# power.net
KiCad netlist of a schematic drawn in Altium Designer
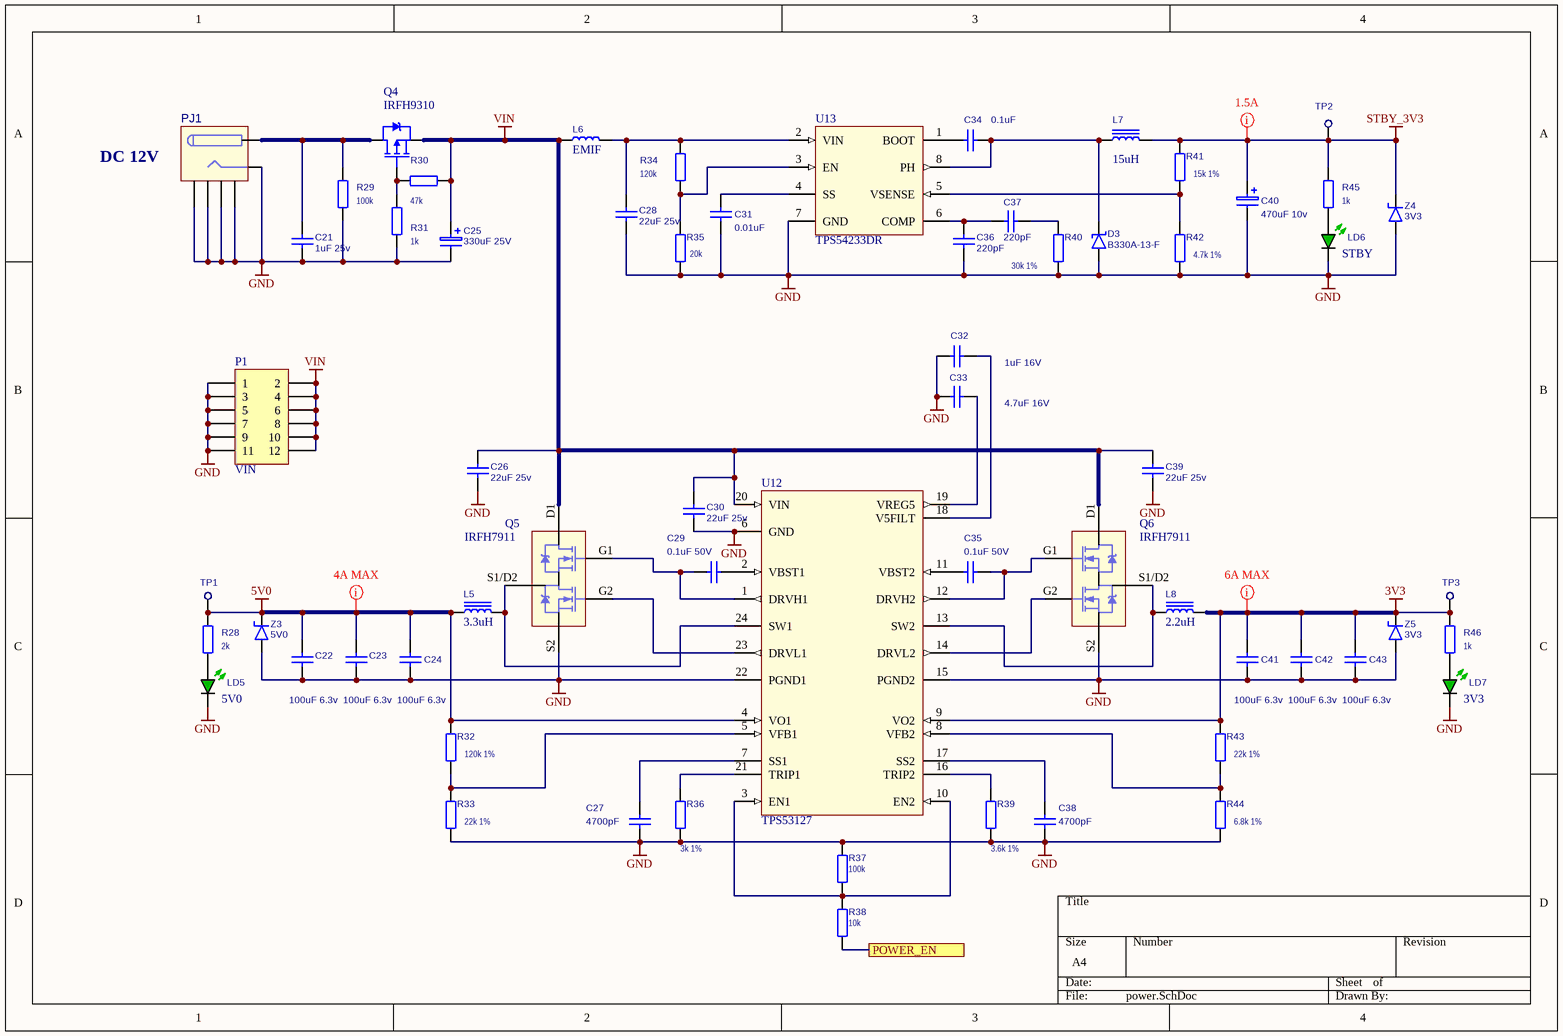
[diagram p0: power.SchDoc]

(export (version "E")
  (design (tool "Eeschema 10.0.6"))
  (components
    (comp (ref "C21")
      (value "1uF 25v")
      (footprint "C0805")
      (description "CAP_NPOL")
      (fields (field (name "Comment") "CL21B105KAFNNNE"))
      (libsource (lib "capacitors") (part "CAP_NPOL"))
    )
    (comp (ref "C22")
      (value "100uF 6.3v")
      (footprint "C1206")
      (description "CAP_NPOL")
      (fields (field (name "Comment") "CL31A107MQHNNNE"))
      (libsource (lib "capacitors") (part "CAP_NPOL"))
    )
    (comp (ref "C23")
      (value "100uF 6.3v")
      (footprint "C1206")
      (description "CAP_NPOL")
      (fields (field (name "Comment") "CL31A107MQHNNNE"))
      (libsource (lib "capacitors") (part "CAP_NPOL"))
    )
    (comp (ref "C24")
      (value "100uF 6.3v")
      (footprint "C1206")
      (description "CAP_NPOL")
      (fields (field (name "Comment") "CL31A107MQHNNNE"))
      (libsource (lib "capacitors") (part "CAP_NPOL"))
    )
    (comp (ref "C25")
      (value "330uF 25V")
      (footprint "Capacitors:R08H04")
      (description "CAP_POL")
      (fields (field (name "Comment") "ECAP 330/25V 0811 105'C"))
      (libsource (lib "capacitors") (part "CAP_POL"))
    )
    (comp (ref "C26")
      (value "22uF 25v")
      (footprint "Capacitors:C0805")
      (description "CAP_NPOL")
      (fields (field (name "Comment") "CL21A226MAQNNNE"))
      (libsource (lib "capacitors") (part "CAP_NPOL"))
    )
    (comp (ref "C27")
      (value "4700pF")
      (footprint "Capacitors:C0603")
      (description "CAP_NPOL")
      (fields (field (name "Comment") "CL10B472KB8NNNC"))
      (libsource (lib "capacitors") (part "CAP_NPOL"))
    )
    (comp (ref "C28")
      (value "22uF 25v")
      (footprint "Capacitors:C0805")
      (description "CAP_NPOL")
      (fields (field (name "Comment") "CL21A226MAQNNNE"))
      (libsource (lib "capacitors") (part "CAP_NPOL"))
    )
    (comp (ref "C29")
      (value "0.1uF 50V")
      (footprint "Capacitors:C0603")
      (description "CAP_NPOL")
      (fields (field (name "Comment") "C1608X7R1H104K080AA"))
      (libsource (lib "capacitors") (part "CAP_NPOL"))
    )
    (comp (ref "C30")
      (value "22uF 25v")
      (footprint "Capacitors:C0805")
      (description "CAP_NPOL")
      (fields (field (name "Comment") "CL21A226MAQNNNE"))
      (libsource (lib "capacitors") (part "CAP_NPOL"))
    )
    (comp (ref "C31")
      (value "0.01uF")
      (footprint "Capacitors:C0603")
      (description "CAP_NPOL")
      (fields (field (name "Comment") "CL10B103KB8NNNC"))
      (libsource (lib "capacitors") (part "CAP_NPOL"))
    )
    (comp (ref "C32")
      (value "1uF 16V")
      (footprint "Capacitors:C0603")
      (description "CAP_NPOL")
      (fields (field (name "Comment") "GRM188R61H105KAALD"))
      (libsource (lib "capacitors") (part "CAP_NPOL"))
    )
    (comp (ref "C33")
      (value "4.7uF 16V")
      (footprint "Capacitors:C0805")
      (description "CAP_NPOL")
      (fields (field (name "Comment") "CL21A475KOFNNNE"))
      (libsource (lib "capacitors") (part "CAP_NPOL"))
    )
    (comp (ref "C34")
      (value "0.1uF")
      (footprint "Capacitors:C0603")
      (description "CAP_NPOL")
      (fields (field (name "Comment") "C1608X7R1H104K080AA"))
      (libsource (lib "capacitors") (part "CAP_NPOL"))
    )
    (comp (ref "C35")
      (value "0.1uF 50V")
      (footprint "Capacitors:C0603")
      (description "CAP_NPOL")
      (fields (field (name "Comment") "C1608X7R1H104K080AA"))
      (libsource (lib "capacitors") (part "CAP_NPOL"))
    )
    (comp (ref "C36")
      (value "220pF")
      (footprint "Capacitors:C0603")
      (description "CAP_NPOL")
      (fields (field (name "Comment") "CL10C221JB8NNNC"))
      (libsource (lib "capacitors") (part "CAP_NPOL"))
    )
    (comp (ref "C37")
      (value "220pF")
      (footprint "Capacitors:C0603")
      (description "CAP_NPOL")
      (fields (field (name "Comment") "CL10C221JB8NNNC"))
      (libsource (lib "capacitors") (part "CAP_NPOL"))
    )
    (comp (ref "C38")
      (value "4700pF")
      (footprint "Capacitors:C0603")
      (description "CAP_NPOL")
      (fields (field (name "Comment") "CL10B472KB8NNNC"))
      (libsource (lib "capacitors") (part "CAP_NPOL"))
    )
    (comp (ref "C39")
      (value "22uF 25v")
      (footprint "Capacitors:C0805")
      (description "CAP_NPOL")
      (fields (field (name "Comment") "CL21A226MAQNNNE"))
      (libsource (lib "capacitors") (part "CAP_NPOL"))
    )
    (comp (ref "C40")
      (value "470uF 10v")
      (footprint "Capacitors:R06H11")
      (description "CAP_POL")
      (fields (field (name "Comment") "ECAP 470/10V 0611 105'C"))
      (libsource (lib "capacitors") (part "CAP_POL"))
    )
    (comp (ref "C41")
      (value "100uF 6.3v")
      (footprint "C1206")
      (description "CAP_NPOL")
      (fields (field (name "Comment") "CL31A107MQHNNNE"))
      (libsource (lib "capacitors") (part "CAP_NPOL"))
    )
    (comp (ref "C42")
      (value "100uF 6.3v")
      (footprint "C1206")
      (description "CAP_NPOL")
      (fields (field (name "Comment") "CL31A107MQHNNNE"))
      (libsource (lib "capacitors") (part "CAP_NPOL"))
    )
    (comp (ref "C43")
      (value "100uF 6.3v")
      (footprint "C1206")
      (description "CAP_NPOL")
      (fields (field (name "Comment") "CL31A107MQHNNNE"))
      (libsource (lib "capacitors") (part "CAP_NPOL"))
    )
    (comp (ref "D3")
      (value "B330A-13-F")
      (footprint "Diodes:SMA")
      (description "SHOTTKY")
      (libsource (lib "diodes") (part "SHOTTKY"))
    )
    (comp (ref "L5")
      (value "3.3uH")
      (footprint "IHLP-2525CZ")
      (description "IND_W_IRON")
      (fields (field (name "Comment") "IHLP2525CZER3R3M01"))
      (libsource (lib "inductors") (part "IND_W_IRON"))
    )
    (comp (ref "L6")
      (value "EMIF")
      (footprint "IND0805")
      (description "IND_WO_IRON")
      (fields (field (name "Comment") "BLM21PG221SN1D"))
      (libsource (lib "inductors") (part "IND_WO_IRON"))
    )
    (comp (ref "L7")
      (value "15uH")
      (footprint "CDRH104R")
      (fields (field (name "Comment") "CDRH104RNP-150NC"))
      (libsource (lib "inductors") (part "IND_W_IRON"))
    )
    (comp (ref "L8")
      (value "2.2uH")
      (footprint "IHLP-2525CZ")
      (description "IND_W_IRON")
      (fields (field (name "Comment") "IHLP2525CZER2R2M01"))
      (libsource (lib "inductors") (part "IND_W_IRON"))
    )
    (comp (ref "LD5")
      (value "5V0")
      (footprint "LED0805")
      (description "LED Green")
      (fields (field (name "Comment") "LED_G"))
      (libsource (lib "leds") (part "LED_GREEN"))
    )
    (comp (ref "LD6")
      (value "STBY")
      (footprint "Leds:LED0805")
      (description "LED Green")
      (fields (field (name "Comment") "LED_G"))
      (libsource (lib "leds") (part "LED_GREEN"))
    )
    (comp (ref "LD7")
      (value "3V3")
      (footprint "LED0805")
      (description "LED Green")
      (fields (field (name "Comment") "LED_G"))
      (libsource (lib "leds") (part "LED_GREEN"))
    )
    (comp (ref "P1")
      (value "VIN")
      (footprint "PLD-6")
      (description "Header, 6-Pin, Dual row")
      (fields (field (name "PUBLISHER") "Altium Limited"))
      (libsource (lib "HDR") (part "HDR 6X2"))
    )
    (comp (ref "PJ1")
      (value "PJ-082BH")
      (footprint "PJ-082BH")
      (description "PowerJack 2P")
      (libsource (lib "PowerJack") (part "PowerJack 2P"))
    )
    (comp (ref "Q4")
      (value "IRFH9310")
      (footprint "PQFN_5X6")
      (description "HEXFET Power MOSFET")
      (libsource (lib "MOSFET") (part "P-Channel"))
    )
    (comp (ref "Q5")
      (value "IRFH7911")
      (footprint "PQFN5X6_DUAL")
      (description "HEXFET Power MOSFET")
      (fields (field (name "Comment") "IRFH7911TR2PBF"))
      (libsource (lib "") (part "IRFH7911_1"))
    )
    (comp (ref "Q6")
      (value "IRFH7911")
      (footprint "PQFN5X6_DUAL")
      (description "HEXFET Power MOSFET")
      (fields (field (name "Comment") "IRFH7911TR2PBF"))
      (libsource (lib "IRFH7911") (part "IRFH7911"))
    )
    (comp (ref "R28")
      (value "2k")
      (footprint "R0603")
      (description "RES")
      (libsource (lib "resistors") (part "RESISTOR"))
    )
    (comp (ref "R29")
      (value "100k")
      (footprint "R0603")
      (description "RES")
      (libsource (lib "resistors") (part "RESISTOR"))
    )
    (comp (ref "R30")
      (value "47k")
      (footprint "R0603")
      (description "RES")
      (libsource (lib "resistors") (part "RESISTOR"))
    )
    (comp (ref "R31")
      (value "1k")
      (footprint "R0603")
      (description "RES")
      (libsource (lib "resistors") (part "RESISTOR"))
    )
    (comp (ref "R32")
      (value "120k 1%")
      (footprint "R0603")
      (description "RES")
      (libsource (lib "resistors") (part "RESISTOR"))
    )
    (comp (ref "R33")
      (value "22k 1%")
      (footprint "R0603")
      (description "RES")
      (libsource (lib "resistors") (part "RESISTOR"))
    )
    (comp (ref "R34")
      (value "120k")
      (footprint "R0603")
      (description "RES")
      (libsource (lib "resistors") (part "RESISTOR"))
    )
    (comp (ref "R35")
      (value "20k")
      (footprint "R0603")
      (description "RES")
      (libsource (lib "resistors") (part "RESISTOR"))
    )
    (comp (ref "R36")
      (value "3k 1%")
      (footprint "R0603")
      (description "RES")
      (libsource (lib "resistors") (part "RESISTOR"))
    )
    (comp (ref "R37")
      (value "100k")
      (footprint "R0603")
      (description "RES")
      (libsource (lib "resistors") (part "RESISTOR"))
    )
    (comp (ref "R38")
      (value "10k")
      (footprint "R0603")
      (description "RES")
      (libsource (lib "resistors") (part "RESISTOR"))
    )
    (comp (ref "R39")
      (value "3.6k 1%")
      (footprint "R0603")
      (description "RES")
      (libsource (lib "resistors") (part "RESISTOR"))
    )
    (comp (ref "R40")
      (value "30k 1%")
      (footprint "R0603")
      (description "RES")
      (libsource (lib "resistors") (part "RESISTOR"))
    )
    (comp (ref "R41")
      (value "15k 1%")
      (footprint "R0603")
      (description "RES")
      (libsource (lib "resistors") (part "RESISTOR"))
    )
    (comp (ref "R42")
      (value "4.7k 1%")
      (footprint "R0603")
      (description "RES")
      (libsource (lib "resistors") (part "RESISTOR"))
    )
    (comp (ref "R43")
      (value "22k 1%")
      (footprint "R0603")
      (description "RES")
      (libsource (lib "resistors") (part "RESISTOR"))
    )
    (comp (ref "R44")
      (value "6.8k 1%")
      (footprint "R0603")
      (description "RES")
      (libsource (lib "resistors") (part "RESISTOR"))
    )
    (comp (ref "R45")
      (value "1k")
      (footprint "R0603")
      (description "RES")
      (libsource (lib "resistors") (part "RESISTOR"))
    )
    (comp (ref "R46")
      (value "1k")
      (footprint "R0603")
      (description "RES")
      (libsource (lib "resistors") (part "RESISTOR"))
    )
    (comp (ref "TP1")
      (value "TEST-POINT")
      (footprint "PAD")
      (description "PCB terminal block")
      (libsource (lib "TestPoint") (part "TEST-POINT"))
    )
    (comp (ref "TP2")
      (value "TEST-POINT")
      (footprint "PAD")
      (description "PCB terminal block")
      (libsource (lib "") (part "TEST-POINT_1"))
    )
    (comp (ref "TP3")
      (value "TEST-POINT")
      (footprint "PAD")
      (description "PCB terminal block")
      (libsource (lib "TestPoint") (part "TEST-POINT"))
    )
    (comp (ref "U12")
      (value "TPS53127")
      (footprint "TSSOP-24")
      (description "Dual Synchronous Step-Down Controller  For Low Voltage Power Rails")
      (libsource (lib "TPS53127") (part "TPS53127"))
    )
    (comp (ref "U13")
      (value "TPS54233DR")
      (footprint "D008_N")
      (description "TPS54232 2-A, 28-V, 300kHz, Step-Down DC-DC Converter With Eco-Mode™")
      (libsource (lib "TPS54232") (part "TPS54232"))
    )
    (comp (ref "Z3")
      (value "5V0")
      (footprint "Diodes:SMB")
      (description "ZENNER")
      (fields (field (name "Comment") "SMBJ5.0A-TR"))
      (libsource (lib "diodes") (part "ZENNER_1"))
    )
    (comp (ref "Z4")
      (value "3V3")
      (footprint "Diodes:SMB")
      (description "ZENNER")
      (fields (field (name "Comment") "SMBJ3V3-E3/52"))
      (libsource (lib "diodes") (part "ZENNER_1"))
    )
    (comp (ref "Z5")
      (value "3V3")
      (footprint "Diodes:SMB")
      (description "ZENNER")
      (fields (field (name "Comment") "SMBJ3V3-E3/52"))
      (libsource (lib "diodes") (part "ZENNER_1"))
    )
  )
  (nets
    (net (code "1") (name "/POWER_EN") (class "Default")
      (node (ref "R38") (pin "1") (pinfunction "1_1") (pintype "passive"))
    )
    (net (code "2") (name "3V3") (class "Default")
      (node (ref "C41") (pin "2") (pinfunction "2_2") (pintype "passive"))
      (node (ref "C42") (pin "2") (pinfunction "2_2") (pintype "passive"))
      (node (ref "C43") (pin "2") (pinfunction "2_2") (pintype "passive"))
      (node (ref "L8") (pin "2") (pintype "passive"))
      (node (ref "R43") (pin "1") (pinfunction "1_1") (pintype "passive"))
      (node (ref "R46") (pin "2") (pinfunction "2_2") (pintype "passive"))
      (node (ref "TP3") (pin "1") (pinfunction "1_1") (pintype "passive"))
      (node (ref "U12") (pin "9") (pinfunction "VO2_9") (pintype "input"))
      (node (ref "Z5") (pin "2") (pinfunction "K_2") (pintype "passive"))
    )
    (net (code "3") (name "5V0") (class "Default")
      (node (ref "C22") (pin "1") (pinfunction "1_1") (pintype "passive"))
      (node (ref "C23") (pin "1") (pinfunction "1_1") (pintype "passive"))
      (node (ref "C24") (pin "2") (pinfunction "2_2") (pintype "passive"))
      (node (ref "L5") (pin "1") (pintype "passive"))
      (node (ref "R28") (pin "2") (pinfunction "2_2") (pintype "passive"))
      (node (ref "R32") (pin "1") (pinfunction "1_1") (pintype "passive"))
      (node (ref "TP1") (pin "1") (pinfunction "1_1") (pintype "passive"))
      (node (ref "U12") (pin "4") (pinfunction "VO1_4") (pintype "input"))
      (node (ref "Z3") (pin "2") (pinfunction "K_2") (pintype "passive"))
    )
    (net (code "4") (name "GND") (class "Default")
      (node (ref "C21") (pin "2") (pinfunction "2_2") (pintype "passive"))
      (node (ref "C22") (pin "2") (pinfunction "2_2") (pintype "passive"))
      (node (ref "C23") (pin "2") (pinfunction "2_2") (pintype "passive"))
      (node (ref "C24") (pin "1") (pinfunction "1_1") (pintype "passive"))
      (node (ref "C25") (pin "2") (pinfunction "-_2") (pintype "passive"))
      (node (ref "C26") (pin "1") (pinfunction "1_1") (pintype "passive"))
      (node (ref "C27") (pin "1") (pinfunction "1_1") (pintype "passive"))
      (node (ref "C28") (pin "1") (pinfunction "1_1") (pintype "passive"))
      (node (ref "C30") (pin "1") (pinfunction "1_1") (pintype "passive"))
      (node (ref "C31") (pin "1") (pinfunction "1_1") (pintype "passive"))
      (node (ref "C32") (pin "1") (pinfunction "1_1") (pintype "passive"))
      (node (ref "C33") (pin "2") (pinfunction "2_2") (pintype "passive"))
      (node (ref "C36") (pin "1") (pinfunction "1_1") (pintype "passive"))
      (node (ref "C38") (pin "1") (pinfunction "1_1") (pintype "passive"))
      (node (ref "C39") (pin "1") (pinfunction "1_1") (pintype "passive"))
      (node (ref "C40") (pin "2") (pinfunction "-_2") (pintype "passive"))
      (node (ref "C41") (pin "1") (pinfunction "1_1") (pintype "passive"))
      (node (ref "C42") (pin "1") (pinfunction "1_1") (pintype "passive"))
      (node (ref "C43") (pin "1") (pinfunction "1_1") (pintype "passive"))
      (node (ref "D3") (pin "1") (pinfunction "A_1") (pintype "passive"))
      (node (ref "LD5") (pin "1") (pintype "passive"))
      (node (ref "LD6") (pin "1") (pintype "passive"))
      (node (ref "LD7") (pin "1") (pintype "passive"))
      (node (ref "P1") (pin "1") (pinfunction "1_1") (pintype "passive"))
      (node (ref "P1") (pin "11") (pinfunction "11_11") (pintype "passive"))
      (node (ref "P1") (pin "3") (pinfunction "3_3") (pintype "passive"))
      (node (ref "P1") (pin "5") (pinfunction "5_5") (pintype "passive"))
      (node (ref "P1") (pin "7") (pinfunction "7_7") (pintype "passive"))
      (node (ref "P1") (pin "9") (pinfunction "9_9") (pintype "passive"))
      (node (ref "PJ1") (pin "2") (pintype "passive"))
      (node (ref "PJ1") (pin "MH1") (pintype "passive"))
      (node (ref "PJ1") (pin "MH2") (pintype "passive"))
      (node (ref "PJ1") (pin "MH3") (pintype "passive"))
      (node (ref "PJ1") (pin "MH4") (pintype "passive"))
      (node (ref "Q5") (pin "S2") (pinfunction "S2_S2") (pintype "passive"))
      (node (ref "Q6") (pin "S2") (pinfunction "S2_S2") (pintype "passive"))
      (node (ref "R29") (pin "2") (pinfunction "2_2") (pintype "passive"))
      (node (ref "R31") (pin "2") (pinfunction "2_2") (pintype "passive"))
      (node (ref "R33") (pin "2") (pinfunction "2_2") (pintype "passive"))
      (node (ref "R35") (pin "2") (pinfunction "2_2") (pintype "passive"))
      (node (ref "R36") (pin "2") (pinfunction "2_2") (pintype "passive"))
      (node (ref "R37") (pin "1") (pinfunction "1_1") (pintype "passive"))
      (node (ref "R39") (pin "2") (pinfunction "2_2") (pintype "passive"))
      (node (ref "R40") (pin "2") (pinfunction "2_2") (pintype "passive"))
      (node (ref "R42") (pin "2") (pinfunction "2_2") (pintype "passive"))
      (node (ref "R44") (pin "2") (pinfunction "2_2") (pintype "passive"))
      (node (ref "U12") (pin "15") (pinfunction "PGND2_15") (pintype "passive"))
      (node (ref "U12") (pin "22") (pinfunction "PGND1_22") (pintype "passive"))
      (node (ref "U12") (pin "6") (pinfunction "GND_6") (pintype "power_in"))
      (node (ref "U13") (pin "7") (pinfunction "GND_7") (pintype "power_in"))
      (node (ref "Z3") (pin "1") (pinfunction "A_1") (pintype "passive"))
      (node (ref "Z4") (pin "1") (pinfunction "A_1") (pintype "passive"))
      (node (ref "Z5") (pin "1") (pinfunction "A_1") (pintype "passive"))
    )
    (net (code "5") (name "Net-(C37-Pad2)") (class "Default")
      (node (ref "C37") (pin "2") (pinfunction "2_2") (pintype "passive"))
      (node (ref "R40") (pin "1") (pinfunction "1_1") (pintype "passive"))
    )
    (net (code "6") (name "Net-(D3-K)") (class "Default")
      (node (ref "C34") (pin "1") (pinfunction "1_1") (pintype "passive"))
      (node (ref "D3") (pin "2") (pinfunction "K_2") (pintype "passive"))
      (node (ref "L7") (pin "1") (pintype "passive"))
      (node (ref "U13") (pin "8") (pinfunction "PH_8") (pintype "output"))
    )
    (net (code "7") (name "Net-(LD5-Pad2)") (class "Default")
      (node (ref "LD5") (pin "2") (pintype "passive"))
      (node (ref "R28") (pin "1") (pinfunction "1_1") (pintype "passive"))
    )
    (net (code "8") (name "Net-(LD6-Pad2)") (class "Default")
      (node (ref "LD6") (pin "2") (pintype "passive"))
      (node (ref "R45") (pin "1") (pinfunction "1_1") (pintype "passive"))
    )
    (net (code "9") (name "Net-(LD7-Pad2)") (class "Default")
      (node (ref "LD7") (pin "2") (pintype "passive"))
      (node (ref "R46") (pin "1") (pinfunction "1_1") (pintype "passive"))
    )
    (net (code "10") (name "Net-(Q4-D)") (class "Default")
      (node (ref "C21") (pin "1") (pinfunction "1_1") (pintype "passive"))
      (node (ref "PJ1") (pin "1") (pintype "passive"))
      (node (ref "Q4") (pin "3") (pinfunction "D_3") (pintype "passive"))
      (node (ref "R29") (pin "1") (pinfunction "1_1") (pintype "passive"))
    )
    (net (code "11") (name "Net-(Q4-G)") (class "Default")
      (node (ref "Q4") (pin "1") (pinfunction "G_1") (pintype "passive"))
      (node (ref "R30") (pin "1") (pinfunction "1_1") (pintype "passive"))
      (node (ref "R31") (pin "1") (pinfunction "1_1") (pintype "passive"))
    )
    (net (code "12") (name "Net-(U12-DRVH1)") (class "Default")
      (node (ref "C29") (pin "2") (pinfunction "2_2") (pintype "passive"))
      (node (ref "Q5") (pin "G1") (pinfunction "G1_G1") (pintype "passive"))
      (node (ref "U12") (pin "1") (pinfunction "DRVH1_1") (pintype "output"))
    )
    (net (code "13") (name "Net-(U12-DRVH2)") (class "Default")
      (node (ref "C35") (pin "1") (pinfunction "1_1") (pintype "passive"))
      (node (ref "Q6") (pin "G1") (pinfunction "G1_G1") (pintype "passive"))
      (node (ref "U12") (pin "12") (pinfunction "DRVH2_12") (pintype "output"))
    )
    (net (code "14") (name "Net-(U12-DRVL1)") (class "Default")
      (node (ref "Q5") (pin "G2") (pinfunction "G2_G2") (pintype "passive"))
      (node (ref "U12") (pin "23") (pinfunction "DRVL1_23") (pintype "output"))
    )
    (net (code "15") (name "Net-(U12-DRVL2)") (class "Default")
      (node (ref "Q6") (pin "G2") (pinfunction "G2_G2") (pintype "passive"))
      (node (ref "U12") (pin "14") (pinfunction "DRVL2_14") (pintype "output"))
    )
    (net (code "16") (name "Net-(U12-EN1)") (class "Default")
      (node (ref "R37") (pin "2") (pinfunction "2_2") (pintype "passive"))
      (node (ref "R38") (pin "2") (pinfunction "2_2") (pintype "passive"))
      (node (ref "U12") (pin "10") (pinfunction "EN2_10") (pintype "input"))
      (node (ref "U12") (pin "3") (pinfunction "EN1_3") (pintype "input"))
    )
    (net (code "17") (name "Net-(U12-SS1)") (class "Default")
      (node (ref "C27") (pin "2") (pinfunction "2_2") (pintype "passive"))
      (node (ref "U12") (pin "7") (pinfunction "SS1_7") (pintype "passive"))
    )
    (net (code "18") (name "Net-(U12-SS2)") (class "Default")
      (node (ref "C38") (pin "2") (pinfunction "2_2") (pintype "passive"))
      (node (ref "U12") (pin "17") (pinfunction "SS2_17") (pintype "passive"))
    )
    (net (code "19") (name "Net-(U12-SW1)") (class "Default")
      (node (ref "L5") (pin "2") (pintype "passive"))
      (node (ref "Q5") (pin "S1/D2") (pinfunction "S1/D2_S1/D2") (pintype "passive"))
      (node (ref "U12") (pin "24") (pinfunction "SW1_24") (pintype "passive"))
    )
    (net (code "20") (name "Net-(U12-SW2)") (class "Default")
      (node (ref "L8") (pin "1") (pintype "passive"))
      (node (ref "Q6") (pin "S1/D2") (pinfunction "S1/D2_S1/D2") (pintype "passive"))
      (node (ref "U12") (pin "13") (pinfunction "SW2_13") (pintype "passive"))
    )
    (net (code "21") (name "Net-(U12-TRIP1)") (class "Default")
      (node (ref "R36") (pin "1") (pinfunction "1_1") (pintype "passive"))
      (node (ref "U12") (pin "21") (pinfunction "TRIP1_21") (pintype "passive"))
    )
    (net (code "22") (name "Net-(U12-TRIP2)") (class "Default")
      (node (ref "R39") (pin "1") (pinfunction "1_1") (pintype "passive"))
      (node (ref "U12") (pin "16") (pinfunction "TRIP2_16") (pintype "passive"))
    )
    (net (code "23") (name "Net-(U12-V5FILT)") (class "Default")
      (node (ref "C32") (pin "2") (pinfunction "2_2") (pintype "passive"))
      (node (ref "U12") (pin "18") (pinfunction "V5FILT_18") (pintype "passive"))
    )
    (net (code "24") (name "Net-(U12-VBST1)") (class "Default")
      (node (ref "C29") (pin "1") (pinfunction "1_1") (pintype "passive"))
      (node (ref "U12") (pin "2") (pinfunction "VBST1_2") (pintype "input"))
    )
    (net (code "25") (name "Net-(U12-VBST2)") (class "Default")
      (node (ref "C35") (pin "2") (pinfunction "2_2") (pintype "passive"))
      (node (ref "U12") (pin "11") (pinfunction "VBST2_11") (pintype "input"))
    )
    (net (code "26") (name "Net-(U12-VFB1)") (class "Default")
      (node (ref "R32") (pin "2") (pinfunction "2_2") (pintype "passive"))
      (node (ref "R33") (pin "1") (pinfunction "1_1") (pintype "passive"))
      (node (ref "U12") (pin "5") (pinfunction "VFB1_5") (pintype "input"))
    )
    (net (code "27") (name "Net-(U12-VFB2)") (class "Default")
      (node (ref "R43") (pin "2") (pinfunction "2_2") (pintype "passive"))
      (node (ref "R44") (pin "1") (pinfunction "1_1") (pintype "passive"))
      (node (ref "U12") (pin "8") (pinfunction "VFB2_8") (pintype "input"))
    )
    (net (code "28") (name "Net-(U12-VREG5)") (class "Default")
      (node (ref "C33") (pin "1") (pinfunction "1_1") (pintype "passive"))
      (node (ref "U12") (pin "19") (pinfunction "VREG5_19") (pintype "output"))
    )
    (net (code "29") (name "Net-(U13-BOOT)") (class "Default")
      (node (ref "C34") (pin "2") (pinfunction "2_2") (pintype "passive"))
      (node (ref "U13") (pin "1") (pinfunction "BOOT_1") (pintype "passive"))
    )
    (net (code "30") (name "Net-(U13-COMP)") (class "Default")
      (node (ref "C36") (pin "2") (pinfunction "2_2") (pintype "passive"))
      (node (ref "C37") (pin "1") (pinfunction "1_1") (pintype "passive"))
      (node (ref "U13") (pin "6") (pinfunction "COMP_6") (pintype "passive"))
    )
    (net (code "31") (name "Net-(U13-EN)") (class "Default")
      (node (ref "R34") (pin "2") (pinfunction "2_2") (pintype "passive"))
      (node (ref "R35") (pin "1") (pinfunction "1_1") (pintype "passive"))
      (node (ref "U13") (pin "3") (pinfunction "EN_3") (pintype "input"))
    )
    (net (code "32") (name "Net-(U13-SS)") (class "Default")
      (node (ref "C31") (pin "2") (pinfunction "2_2") (pintype "passive"))
      (node (ref "U13") (pin "4") (pinfunction "SS_4") (pintype "passive"))
    )
    (net (code "33") (name "Net-(U13-VIN)") (class "Default")
      (node (ref "C28") (pin "2") (pinfunction "2_2") (pintype "passive"))
      (node (ref "L6") (pin "1") (pintype "passive"))
      (node (ref "R34") (pin "1") (pinfunction "1_1") (pintype "passive"))
      (node (ref "U13") (pin "2") (pinfunction "VIN_2") (pintype "input"))
    )
    (net (code "34") (name "Net-(U13-VSENSE)") (class "Default")
      (node (ref "R41") (pin "2") (pinfunction "2_2") (pintype "passive"))
      (node (ref "R42") (pin "1") (pinfunction "1_1") (pintype "passive"))
      (node (ref "U13") (pin "5") (pinfunction "VSENSE_5") (pintype "input"))
    )
    (net (code "35") (name "STBY_3V3") (class "Default")
      (node (ref "C40") (pin "1") (pinfunction "+_1") (pintype "passive"))
      (node (ref "L7") (pin "2") (pintype "passive"))
      (node (ref "R41") (pin "1") (pinfunction "1_1") (pintype "passive"))
      (node (ref "R45") (pin "2") (pinfunction "2_2") (pintype "passive"))
      (node (ref "TP2") (pin "1") (pinfunction "1_1") (pintype "passive"))
      (node (ref "Z4") (pin "2") (pinfunction "K_2") (pintype "passive"))
    )
    (net (code "36") (name "VIN") (class "Default")
      (node (ref "C25") (pin "1") (pinfunction "+_1") (pintype "passive"))
      (node (ref "C26") (pin "2") (pinfunction "2_2") (pintype "passive"))
      (node (ref "C30") (pin "2") (pinfunction "2_2") (pintype "passive"))
      (node (ref "C39") (pin "2") (pinfunction "2_2") (pintype "passive"))
      (node (ref "L6") (pin "2") (pintype "passive"))
      (node (ref "P1") (pin "10") (pinfunction "10_10") (pintype "passive"))
      (node (ref "P1") (pin "12") (pinfunction "12_12") (pintype "passive"))
      (node (ref "P1") (pin "2") (pinfunction "2_2") (pintype "passive"))
      (node (ref "P1") (pin "4") (pinfunction "4_4") (pintype "passive"))
      (node (ref "P1") (pin "6") (pinfunction "6_6") (pintype "passive"))
      (node (ref "P1") (pin "8") (pinfunction "8_8") (pintype "passive"))
      (node (ref "Q4") (pin "2") (pinfunction "S_2") (pintype "passive"))
      (node (ref "Q5") (pin "D1") (pinfunction "D1_D1") (pintype "passive"))
      (node (ref "Q6") (pin "D1") (pinfunction "D1_D1") (pintype "passive"))
      (node (ref "R30") (pin "2") (pinfunction "2_2") (pintype "passive"))
      (node (ref "U12") (pin "20") (pinfunction "VIN_20") (pintype "input"))
    )
  )
)
